# Sheet1.net
KiCad netlist of a schematic drawn in Altium Designer
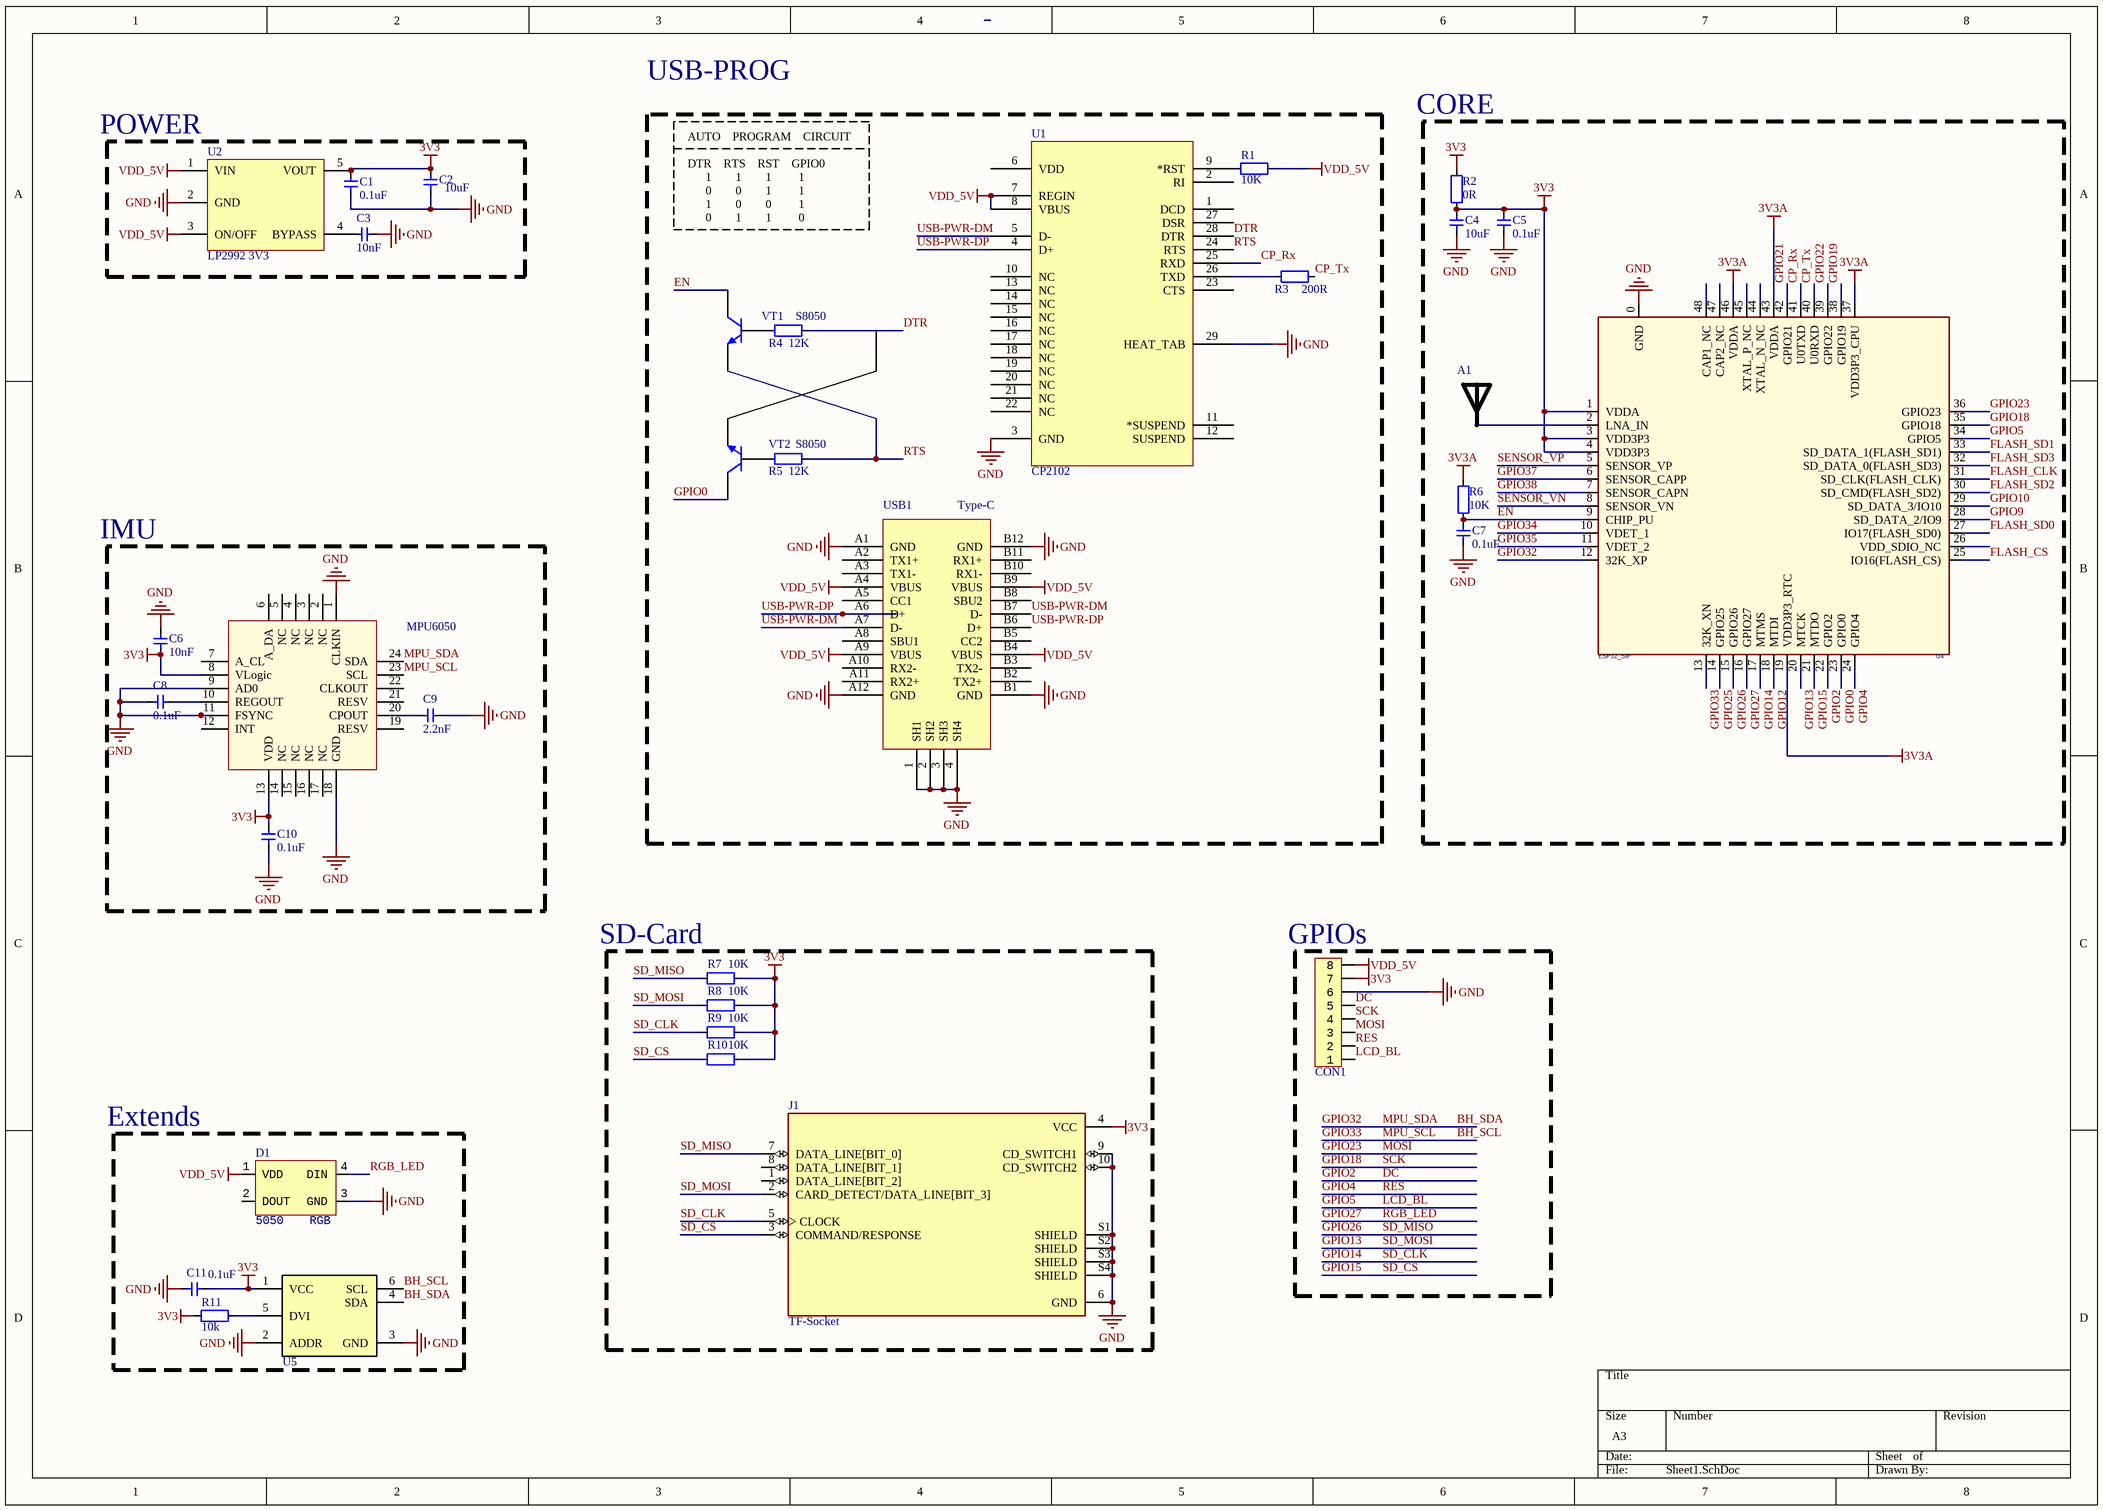
[diagram p0: Sheet1.SchDoc]

(export (version "E")
  (design (tool "Eeschema 10.0.6"))
  (components
    (comp (ref "A1")
      (value "RAINSUN")
      (footprint "ANT-Rainsun-AN5120")
      (libsource (lib "MainBoard") (part "ANT-Rainsun-AP5120"))
    )
    (comp (ref "C1")
      (value "0.1uF")
      (footprint "CAP_0402")
      (description "Capacitor")
      (libsource (lib "MainBoard") (part "电容-0402_3"))
    )
    (comp (ref "C2")
      (value "10uF")
      (footprint "CAP_0402")
      (description "Capacitor")
      (libsource (lib "MainBoard") (part "电容-0402_3"))
    )
    (comp (ref "C3")
      (value "10nF")
      (footprint "CAP_0402")
      (description "Capacitor")
      (libsource (lib "MainBoard") (part "电容-0402_3"))
    )
    (comp (ref "C4")
      (value "10uF")
      (footprint "CAP_0402")
      (description "Capacitor")
      (libsource (lib "MainBoard") (part "电容-0402_1"))
    )
    (comp (ref "C5")
      (value "0.1uF")
      (footprint "CAP_0402")
      (description "Capacitor")
      (libsource (lib "MainBoard") (part "电容-0402_1"))
    )
    (comp (ref "C6")
      (value "10nF")
      (footprint "CAP_0402")
      (description "Capacitor")
      (libsource (lib "MainBoard") (part "电容-0402"))
    )
    (comp (ref "C7")
      (value "0.1uF")
      (footprint "CAP_0402")
      (description "Capacitor")
      (libsource (lib "MainBoard") (part "电容-0402_1"))
    )
    (comp (ref "C8")
      (value "0.1uF")
      (footprint "CAP_0402")
      (description "Capacitor")
      (libsource (lib "MainBoard") (part "电容-0402"))
    )
    (comp (ref "C9")
      (value "2.2nF")
      (footprint "CAP_0402")
      (description "Capacitor")
      (libsource (lib "MainBoard") (part "电容-0402"))
    )
    (comp (ref "C10")
      (value "0.1uF")
      (footprint "CAP_0402")
      (description "Capacitor")
      (libsource (lib "MainBoard") (part "电容-0402"))
    )
    (comp (ref "C11")
      (value "0.1uF")
      (footprint "CAP_0402")
      (description "Capacitor")
      (libsource (lib "MainBoard") (part "电容-0402"))
    )
    (comp (ref "CON1")
      (value "FFC_0.5_8")
      (footprint "FFC_0.5_8")
      (description "FFC")
      (libsource (lib "MainBoard") (part "FFC_0.5_8"))
    )
    (comp (ref "D1")
      (value "RGB")
      (footprint "LED_5050_WS2812B")
      (description "LED")
      (fields (field (name "TYPE") "5050"))
      (libsource (lib "MainBoard") (part "LED_5050_WS2812B"))
    )
    (comp (ref "J1")
      (value "TF-Socket")
      (footprint "TF-Card-Amphenol with TF")
      (description "10 _8 + 2_ Position Card Connector Secure Digital - microSDâ„¢ Surface Mount, Right Angle Gold")
      (fields (field (name "MP") "1140084168") (field (name "MF") "Amphenol Commercial Products"))
      (libsource (lib "MainBoard") (part "TF-Socket"))
    )
    (comp (ref "R1")
      (value "10K")
      (footprint "RES_0402")
      (description "Resistor")
      (libsource (lib "MainBoard") (part "电阻-0402_1"))
    )
    (comp (ref "R2")
      (value "0R")
      (footprint "RES_0402")
      (description "Resistor")
      (libsource (lib "") (part "电阻-0402_1_1"))
    )
    (comp (ref "R3")
      (value "200R")
      (footprint "RES_0402")
      (description "Resistor")
      (libsource (lib "MainBoard") (part "电阻-0402_1"))
    )
    (comp (ref "R4")
      (value "12K")
      (footprint "RES_0402")
      (description "Resistor")
      (libsource (lib "MainBoard") (part "电阻-0402_1"))
    )
    (comp (ref "R5")
      (value "12K")
      (footprint "RES_0402")
      (description "Resistor")
      (libsource (lib "MainBoard") (part "电阻-0402_1"))
    )
    (comp (ref "R6")
      (value "10K")
      (footprint "RES_0402")
      (description "Resistor")
      (libsource (lib "") (part "电阻-0402_1_1"))
    )
    (comp (ref "R7")
      (value "10K")
      (footprint "RES_0402")
      (description "Resistor")
      (libsource (lib "MainBoard") (part "电阻-0402"))
    )
    (comp (ref "R8")
      (value "10K")
      (footprint "RES_0402")
      (description "Resistor")
      (libsource (lib "MainBoard") (part "电阻-0402"))
    )
    (comp (ref "R9")
      (value "10K")
      (footprint "RES_0402")
      (description "Resistor")
      (libsource (lib "MainBoard") (part "电阻-0402"))
    )
    (comp (ref "R10")
      (value "10K")
      (footprint "RES_0402")
      (description "Resistor")
      (libsource (lib "MainBoard") (part "电阻-0402"))
    )
    (comp (ref "R11")
      (value "10k")
      (footprint "RES_0402")
      (description "Resistor")
      (libsource (lib "MainBoard") (part "电阻-0402"))
    )
    (comp (ref "U1")
      (value "CP2102")
      (footprint "QFN-28")
      (description "USB转TTL")
      (libsource (lib "MainBoard") (part "CP2102"))
    )
    (comp (ref "U2")
      (value "LP2992 3V3")
      (footprint "SOT23-5")
      (description "LDO")
      (libsource (lib "MainBoard") (part "LP2992"))
    )
    (comp (ref "U3")
      (value "MPU6050")
      (footprint "QFN-24")
      (description "六轴传感器")
      (libsource (lib "MainBoard") (part "MPU6050"))
    )
    (comp (ref "U4")
      (value "ESP32_SIP")
      (footprint "QFN-48_7X7")
      (libsource (lib "MainBoard") (part "ESP32-PICO"))
    )
    (comp (ref "U5")
      (value "BH1750FVI-TR")
      (footprint "BH1750FVI")
      (libsource (lib "MainBoard") (part "BH1750FVI-TR"))
    )
    (comp (ref "USB1")
      (value "Type-C")
      (footprint "Type-C-TOP")
      (libsource (lib "MainBoard") (part "USB-Type-C-TOP"))
    )
    (comp (ref "VT1")
      (value "S8050")
      (footprint "SMT_TRIODE_NPN")
      (description "Surface mount NPN transistor, package SOT-23")
      (libsource (lib "MainBoard") (part "SMT_TRIODE_NPN"))
    )
    (comp (ref "VT2")
      (value "S8050")
      (footprint "SMT_TRIODE_NPN")
      (description "Surface mount NPN transistor, package SOT-23")
      (libsource (lib "MainBoard") (part "SMT_TRIODE_NPN"))
    )
  )
  (nets
    (net (code "1") (name "/BH_SCL") (class "Default")
      (node (ref "U3") (pin "23") (pinfunction "SCL_23") (pintype "passive"))
      (node (ref "U4") (pin "13") (pinfunction "32K_XN_13") (pintype "passive"))
      (node (ref "U5") (pin "6") (pinfunction "SCL_6") (pintype "passive"))
    )
    (net (code "2") (name "/BH_SDA") (class "Default")
      (node (ref "U3") (pin "24") (pinfunction "SDA_24") (pintype "passive"))
      (node (ref "U4") (pin "12") (pinfunction "32K_XP_12") (pintype "passive"))
      (node (ref "U5") (pin "4") (pinfunction "SDA_4") (pintype "passive"))
    )
    (net (code "3") (name "/CP_Rx") (class "Default")
      (node (ref "U1") (pin "25") (pinfunction "RXD_25") (pintype "passive"))
      (node (ref "U4") (pin "41") (pinfunction "U0TXD_41") (pintype "power_in"))
    )
    (net (code "4") (name "/CP_Tx") (class "Default")
      (node (ref "R3") (pin "1") (pinfunction "1_1") (pintype "passive"))
      (node (ref "U4") (pin "40") (pinfunction "U0RXD_40") (pintype "power_in"))
    )
    (net (code "5") (name "/DC") (class "Default")
      (node (ref "CON1") (pin "5") (pinfunction "5_5") (pintype "passive"))
      (node (ref "U4") (pin "22") (pinfunction "GPIO2_22") (pintype "passive"))
    )
    (net (code "6") (name "/DTR") (class "Default")
      (node (ref "R4") (pin "1") (pinfunction "1_1") (pintype "passive"))
      (node (ref "U1") (pin "28") (pinfunction "DTR_28") (pintype "passive"))
    )
    (net (code "7") (name "/EN") (class "Default")
      (node (ref "C7") (pin "1") (pinfunction "1_1") (pintype "passive"))
      (node (ref "R6") (pin "1") (pinfunction "1_1") (pintype "passive"))
      (node (ref "U4") (pin "9") (pinfunction "CHIP_PU_9") (pintype "passive"))
      (node (ref "VT1") (pin "3") (pinfunction "C_3") (pintype "passive"))
    )
    (net (code "8") (name "/FLASH_CLK") (class "Default")
      (node (ref "U4") (pin "31") (pinfunction "SD_CLK(FLASH_CLK)_31") (pintype "passive"))
    )
    (net (code "9") (name "/FLASH_CS") (class "Default")
      (node (ref "U4") (pin "25") (pinfunction "IO16(FLASH_CS)_25") (pintype "passive"))
    )
    (net (code "10") (name "/FLASH_SD0") (class "Default")
      (node (ref "U4") (pin "27") (pinfunction "IO17(FLASH_SD0)_27") (pintype "passive"))
    )
    (net (code "11") (name "/FLASH_SD1") (class "Default")
      (node (ref "U4") (pin "33") (pinfunction "SD_DATA_1(FLASH_SD1)_33") (pintype "passive"))
    )
    (net (code "12") (name "/FLASH_SD2") (class "Default")
      (node (ref "U4") (pin "30") (pinfunction "SD_CMD(FLASH_SD2)_30") (pintype "passive"))
    )
    (net (code "13") (name "/FLASH_SD3") (class "Default")
      (node (ref "U4") (pin "32") (pinfunction "SD_DATA_0(FLASH_SD3)_32") (pintype "passive"))
    )
    (net (code "14") (name "/GPIO0") (class "Default")
      (node (ref "U4") (pin "23") (pinfunction "GPIO0_23") (pintype "passive"))
      (node (ref "VT2") (pin "3") (pinfunction "C_3") (pintype "passive"))
    )
    (net (code "15") (name "/GPIO4") (class "Default")
      (node (ref "CON1") (pin "2") (pinfunction "2_2") (pintype "passive"))
      (node (ref "U4") (pin "24") (pinfunction "GPIO4_24") (pintype "passive"))
    )
    (net (code "16") (name "/GPIO5") (class "Default")
      (node (ref "CON1") (pin "1") (pinfunction "1_1") (pintype "passive"))
      (node (ref "U4") (pin "34") (pinfunction "GPIO5_34") (pintype "passive"))
    )
    (net (code "17") (name "/GPIO9") (class "Default")
      (node (ref "U4") (pin "28") (pinfunction "SD_DATA_2/IO9_28") (pintype "passive"))
    )
    (net (code "18") (name "/GPIO10") (class "Default")
      (node (ref "U4") (pin "29") (pinfunction "SD_DATA_3/IO10_29") (pintype "passive"))
    )
    (net (code "19") (name "/GPIO12") (class "Default")
      (node (ref "U4") (pin "18") (pinfunction "MTDI_18") (pintype "passive"))
    )
    (net (code "20") (name "/GPIO13") (class "Default")
      (node (ref "J1") (pin "2") (pinfunction "CARD_DETECT/DATA_LINE[BIT_3]_2") (pintype "bidirectional"))
      (node (ref "R8") (pin "1") (pinfunction "1_1") (pintype "passive"))
      (node (ref "U4") (pin "20") (pinfunction "MTCK_20") (pintype "passive"))
    )
    (net (code "21") (name "/GPIO14") (class "Default")
      (node (ref "J1") (pin "5") (pinfunction "CLOCK_5") (pintype "bidirectional"))
      (node (ref "R9") (pin "1") (pinfunction "1_1") (pintype "passive"))
      (node (ref "U4") (pin "17") (pinfunction "MTMS_17") (pintype "passive"))
    )
    (net (code "22") (name "/GPIO15") (class "Default")
      (node (ref "J1") (pin "3") (pinfunction "COMMAND/RESPONSE_3") (pintype "bidirectional"))
      (node (ref "R10") (pin "1") (pinfunction "1_1") (pintype "passive"))
      (node (ref "U4") (pin "21") (pinfunction "MTDO_21") (pintype "passive"))
    )
    (net (code "23") (name "/GPIO18") (class "Default")
      (node (ref "CON1") (pin "4") (pinfunction "4_4") (pintype "passive"))
      (node (ref "U4") (pin "35") (pinfunction "GPIO18_35") (pintype "passive"))
    )
    (net (code "24") (name "/GPIO19") (class "Default")
      (node (ref "U4") (pin "38") (pinfunction "GPIO19_38") (pintype "passive"))
    )
    (net (code "25") (name "/GPIO21") (class "Default")
      (node (ref "U4") (pin "42") (pinfunction "GPIO21_42") (pintype "passive"))
    )
    (net (code "26") (name "/GPIO22") (class "Default")
      (node (ref "U4") (pin "39") (pinfunction "GPIO22_39") (pintype "passive"))
    )
    (net (code "27") (name "/GPIO23") (class "Default")
      (node (ref "CON1") (pin "3") (pinfunction "3_3") (pintype "passive"))
      (node (ref "U4") (pin "36") (pinfunction "GPIO23_36") (pintype "passive"))
    )
    (net (code "28") (name "/GPIO25") (class "Default")
      (node (ref "U4") (pin "14") (pinfunction "GPIO25_14") (pintype "passive"))
    )
    (net (code "29") (name "/GPIO26") (class "Default")
      (node (ref "J1") (pin "7") (pinfunction "DATA_LINE[BIT_0]_7") (pintype "bidirectional"))
      (node (ref "R7") (pin "1") (pinfunction "1_1") (pintype "passive"))
      (node (ref "U4") (pin "15") (pinfunction "GPIO26_15") (pintype "passive"))
    )
    (net (code "30") (name "/GPIO27") (class "Default")
      (node (ref "D1") (pin "4") (pinfunction "DIN_4") (pintype "passive"))
      (node (ref "U4") (pin "16") (pinfunction "GPIO27_16") (pintype "passive"))
    )
    (net (code "31") (name "/GPIO34") (class "Default")
      (node (ref "U4") (pin "10") (pinfunction "VDET_1_10") (pintype "passive"))
    )
    (net (code "32") (name "/GPIO35") (class "Default")
      (node (ref "U4") (pin "11") (pinfunction "VDET_2_11") (pintype "passive"))
    )
    (net (code "33") (name "/GPIO37") (class "Default")
      (node (ref "U4") (pin "6") (pinfunction "SENSOR_CAPP_6") (pintype "passive"))
    )
    (net (code "34") (name "/GPIO38") (class "Default")
      (node (ref "U4") (pin "7") (pinfunction "SENSOR_CAPN_7") (pintype "passive"))
    )
    (net (code "35") (name "/RTS") (class "Default")
      (node (ref "R5") (pin "1") (pinfunction "1_1") (pintype "passive"))
      (node (ref "U1") (pin "24") (pinfunction "RTS_24") (pintype "passive"))
      (node (ref "VT1") (pin "2") (pinfunction "E_2") (pintype "passive"))
    )
    (net (code "36") (name "/SENSOR_VN") (class "Default")
      (node (ref "U4") (pin "8") (pinfunction "SENSOR_VN_8") (pintype "passive"))
    )
    (net (code "37") (name "/SENSOR_VP") (class "Default")
      (node (ref "U4") (pin "5") (pinfunction "SENSOR_VP_5") (pintype "passive"))
    )
    (net (code "38") (name "/USB-PWR-DM") (class "Default")
      (node (ref "U1") (pin "5") (pinfunction "D-_5") (pintype "passive"))
      (node (ref "USB1") (pin "A7") (pinfunction "D-_A7") (pintype "passive"))
      (node (ref "USB1") (pin "B7") (pinfunction "D-_B7") (pintype "passive"))
    )
    (net (code "39") (name "/USB-PWR-DP") (class "Default")
      (node (ref "U1") (pin "4") (pinfunction "D+_4") (pintype "passive"))
      (node (ref "USB1") (pin "A6") (pinfunction "D+_A6") (pintype "passive"))
      (node (ref "USB1") (pin "B6") (pinfunction "D+_B6") (pintype "passive"))
    )
    (net (code "40") (name "3V3") (class "Default")
      (node (ref "C1") (pin "2") (pinfunction "2_2") (pintype "passive"))
      (node (ref "C10") (pin "1") (pinfunction "1_1") (pintype "passive"))
      (node (ref "C11") (pin "1") (pinfunction "1_1") (pintype "passive"))
      (node (ref "C2") (pin "2") (pinfunction "2_2") (pintype "passive"))
      (node (ref "C4") (pin "1") (pinfunction "1_1") (pintype "passive"))
      (node (ref "C5") (pin "1") (pinfunction "1_1") (pintype "passive"))
      (node (ref "C6") (pin "1") (pinfunction "1_1") (pintype "passive"))
      (node (ref "CON1") (pin "7") (pinfunction "7_7") (pintype "passive"))
      (node (ref "J1") (pin "4") (pinfunction "VCC_4") (pintype "power_in"))
      (node (ref "R10") (pin "2") (pinfunction "2_2") (pintype "passive"))
      (node (ref "R11") (pin "1") (pinfunction "1_1") (pintype "passive"))
      (node (ref "R2") (pin "1") (pinfunction "1_1") (pintype "passive"))
      (node (ref "R2") (pin "2") (pinfunction "2_2") (pintype "passive"))
      (node (ref "R7") (pin "2") (pinfunction "2_2") (pintype "passive"))
      (node (ref "R8") (pin "2") (pinfunction "2_2") (pintype "passive"))
      (node (ref "R9") (pin "2") (pinfunction "2_2") (pintype "passive"))
      (node (ref "U2") (pin "5") (pinfunction "VOUT_5") (pintype "passive"))
      (node (ref "U3") (pin "13") (pinfunction "VDD_13") (pintype "passive"))
      (node (ref "U3") (pin "8") (pinfunction "VLogic_8") (pintype "passive"))
      (node (ref "U4") (pin "1") (pinfunction "VDDA_1") (pintype "power_in"))
      (node (ref "U4") (pin "3") (pinfunction "VDD3P3_3") (pintype "power_in"))
      (node (ref "U4") (pin "4") (pinfunction "VDD3P3_4") (pintype "power_in"))
      (node (ref "U5") (pin "1") (pinfunction "VCC_1") (pintype "passive"))
    )
    (net (code "41") (name "3V3A") (class "Default")
      (node (ref "R6") (pin "2") (pinfunction "2_2") (pintype "passive"))
      (node (ref "U4") (pin "19") (pinfunction "VDD3P3_RTC_19") (pintype "power_in"))
      (node (ref "U4") (pin "37") (pinfunction "VDD3P3_CPU_37") (pintype "power_in"))
      (node (ref "U4") (pin "43") (pinfunction "VDDA_43") (pintype "power_in"))
      (node (ref "U4") (pin "46") (pinfunction "VDDA_46") (pintype "power_in"))
    )
    (net (code "42") (name "GND") (class "Default")
      (node (ref "C1") (pin "1") (pinfunction "1_1") (pintype "passive"))
      (node (ref "C10") (pin "2") (pinfunction "2_2") (pintype "passive"))
      (node (ref "C11") (pin "2") (pinfunction "2_2") (pintype "passive"))
      (node (ref "C2") (pin "1") (pinfunction "1_1") (pintype "passive"))
      (node (ref "C3") (pin "2") (pinfunction "2_2") (pintype "passive"))
      (node (ref "C4") (pin "2") (pinfunction "2_2") (pintype "passive"))
      (node (ref "C5") (pin "2") (pinfunction "2_2") (pintype "passive"))
      (node (ref "C6") (pin "2") (pinfunction "2_2") (pintype "passive"))
      (node (ref "C7") (pin "2") (pinfunction "2_2") (pintype "passive"))
      (node (ref "C8") (pin "1") (pinfunction "1_1") (pintype "passive"))
      (node (ref "C9") (pin "2") (pinfunction "2_2") (pintype "passive"))
      (node (ref "CON1") (pin "6") (pinfunction "6_6") (pintype "passive"))
      (node (ref "D1") (pin "3") (pinfunction "GND_3") (pintype "passive"))
      (node (ref "J1") (pin "10") (pinfunction "CD_SWITCH2_10") (pintype "bidirectional"))
      (node (ref "J1") (pin "6") (pinfunction "GND_6") (pintype "power_in"))
      (node (ref "J1") (pin "9") (pinfunction "CD_SWITCH1_9") (pintype "bidirectional"))
      (node (ref "J1") (pin "S1") (pinfunction "SHIELD_S1") (pintype "passive"))
      (node (ref "J1") (pin "S2") (pinfunction "SHIELD_S2") (pintype "passive"))
      (node (ref "J1") (pin "S3") (pinfunction "SHIELD_S3") (pintype "passive"))
      (node (ref "J1") (pin "S4") (pinfunction "SHIELD_S4") (pintype "passive"))
      (node (ref "U1") (pin "29") (pinfunction "HEAT_TAB_29") (pintype "passive"))
      (node (ref "U1") (pin "3") (pinfunction "GND_3") (pintype "passive"))
      (node (ref "U2") (pin "2") (pinfunction "GND_2") (pintype "passive"))
      (node (ref "U3") (pin "1") (pinfunction "CLKIN_1") (pintype "passive"))
      (node (ref "U3") (pin "11") (pinfunction "FSYNC_11") (pintype "passive"))
      (node (ref "U3") (pin "18") (pinfunction "GND_18") (pintype "passive"))
      (node (ref "U3") (pin "9") (pinfunction "AD0_9") (pintype "passive"))
      (node (ref "U4") (pin "0") (pinfunction "GND_0") (pintype "power_in"))
      (node (ref "U5") (pin "2") (pinfunction "ADDR_2") (pintype "passive"))
      (node (ref "U5") (pin "3") (pinfunction "GND_3") (pintype "passive"))
      (node (ref "USB1") (pin "1") (pinfunction "SH1_1") (pintype "passive"))
      (node (ref "USB1") (pin "2") (pinfunction "SH2_2") (pintype "passive"))
      (node (ref "USB1") (pin "3") (pinfunction "SH3_3") (pintype "passive"))
      (node (ref "USB1") (pin "4") (pinfunction "SH4_4") (pintype "passive"))
      (node (ref "USB1") (pin "A1") (pinfunction "GND_A1") (pintype "passive"))
      (node (ref "USB1") (pin "A12") (pinfunction "GND_A12") (pintype "passive"))
      (node (ref "USB1") (pin "B1") (pinfunction "GND_B1") (pintype "passive"))
      (node (ref "USB1") (pin "B12") (pinfunction "GND_B12") (pintype "passive"))
    )
    (net (code "43") (name "Net-(U1-*RST)") (class "Default")
      (node (ref "R1") (pin "2") (pinfunction "2_2") (pintype "passive"))
      (node (ref "U1") (pin "9") (pinfunction "*RST_9") (pintype "passive"))
    )
    (net (code "44") (name "Net-(U1-TXD)") (class "Default")
      (node (ref "R3") (pin "2") (pinfunction "2_2") (pintype "passive"))
      (node (ref "U1") (pin "26") (pinfunction "TXD_26") (pintype "passive"))
    )
    (net (code "45") (name "Net-(U2-BYPASS)") (class "Default")
      (node (ref "C3") (pin "1") (pinfunction "1_1") (pintype "passive"))
      (node (ref "U2") (pin "4") (pinfunction "BYPASS_4") (pintype "passive"))
    )
    (net (code "46") (name "Net-(U3-CPOUT)") (class "Default")
      (node (ref "C9") (pin "1") (pinfunction "1_1") (pintype "passive"))
      (node (ref "U3") (pin "20") (pinfunction "CPOUT_20") (pintype "passive"))
    )
    (net (code "47") (name "Net-(U3-REGOUT)") (class "Default")
      (node (ref "C8") (pin "2") (pinfunction "2_2") (pintype "passive"))
      (node (ref "U3") (pin "10") (pinfunction "REGOUT_10") (pintype "passive"))
    )
    (net (code "48") (name "Net-(U4-LNA_IN)") (class "Default")
      (node (ref "A1") (pin "1") (pinfunction "1_1") (pintype "passive"))
      (node (ref "U4") (pin "2") (pinfunction "LNA_IN_2") (pintype "passive"))
    )
    (net (code "49") (name "Net-(U5-DVI)") (class "Default")
      (node (ref "R11") (pin "2") (pinfunction "2_2") (pintype "passive"))
      (node (ref "U5") (pin "5") (pinfunction "DVI_5") (pintype "passive"))
    )
    (net (code "50") (name "Net-(VT1-B)") (class "Default")
      (node (ref "R4") (pin "2") (pinfunction "2_2") (pintype "passive"))
      (node (ref "VT1") (pin "1") (pinfunction "B_1") (pintype "passive"))
    )
    (net (code "51") (name "Net-(VT2-B)") (class "Default")
      (node (ref "R5") (pin "2") (pinfunction "2_2") (pintype "passive"))
      (node (ref "VT2") (pin "1") (pinfunction "B_1") (pintype "passive"))
    )
    (net (code "52") (name "VDD_5V") (class "Default")
      (node (ref "CON1") (pin "8") (pinfunction "8_8") (pintype "passive"))
      (node (ref "D1") (pin "1") (pinfunction "VDD_1") (pintype "passive"))
      (node (ref "R1") (pin "1") (pinfunction "1_1") (pintype "passive"))
      (node (ref "U1") (pin "7") (pinfunction "REGIN_7") (pintype "passive"))
      (node (ref "U1") (pin "8") (pinfunction "VBUS_8") (pintype "passive"))
      (node (ref "U2") (pin "1") (pinfunction "VIN_1") (pintype "passive"))
      (node (ref "U2") (pin "3") (pinfunction "ON/OFF_3") (pintype "passive"))
      (node (ref "USB1") (pin "A4") (pinfunction "VBUS_A4") (pintype "passive"))
      (node (ref "USB1") (pin "A9") (pinfunction "VBUS_A9") (pintype "passive"))
      (node (ref "USB1") (pin "B4") (pinfunction "VBUS_B4") (pintype "passive"))
      (node (ref "USB1") (pin "B9") (pinfunction "VBUS_B9") (pintype "passive"))
    )
    (net (code "53") (name "unconnected-(D1-DOUT-Pad2)") (class "Default")
      (node (ref "D1") (pin "2") (pinfunction "DOUT_2") (pintype "passive"))
    )
    (net (code "54") (name "unconnected-(J1-DATA_LINE[BIT_1]-Pad8)") (class "Default")
      (node (ref "J1") (pin "8") (pinfunction "DATA_LINE[BIT_1]_8") (pintype "bidirectional"))
    )
    (net (code "55") (name "unconnected-(J1-DATA_LINE[BIT_2]-Pad1)") (class "Default")
      (node (ref "J1") (pin "1") (pinfunction "DATA_LINE[BIT_2]_1") (pintype "bidirectional"))
    )
    (net (code "56") (name "unconnected-(U1-*SUSPEND-Pad11)") (class "Default")
      (node (ref "U1") (pin "11") (pinfunction "*SUSPEND_11") (pintype "passive"))
    )
    (net (code "57") (name "unconnected-(U1-CTS-Pad23)") (class "Default")
      (node (ref "U1") (pin "23") (pinfunction "CTS_23") (pintype "passive"))
    )
    (net (code "58") (name "unconnected-(U1-DCD-Pad1)") (class "Default")
      (node (ref "U1") (pin "1") (pinfunction "DCD_1") (pintype "passive"))
    )
    (net (code "59") (name "unconnected-(U1-DSR-Pad27)") (class "Default")
      (node (ref "U1") (pin "27") (pinfunction "DSR_27") (pintype "passive"))
    )
    (net (code "60") (name "unconnected-(U1-NC-Pad10)") (class "Default")
      (node (ref "U1") (pin "10") (pinfunction "NC_10") (pintype "passive"))
    )
    (net (code "61") (name "unconnected-(U1-NC-Pad13)") (class "Default")
      (node (ref "U1") (pin "13") (pinfunction "NC_13") (pintype "passive"))
    )
    (net (code "62") (name "unconnected-(U1-NC-Pad14)") (class "Default")
      (node (ref "U1") (pin "14") (pinfunction "NC_14") (pintype "passive"))
    )
    (net (code "63") (name "unconnected-(U1-NC-Pad15)") (class "Default")
      (node (ref "U1") (pin "15") (pinfunction "NC_15") (pintype "passive"))
    )
    (net (code "64") (name "unconnected-(U1-NC-Pad16)") (class "Default")
      (node (ref "U1") (pin "16") (pinfunction "NC_16") (pintype "passive"))
    )
    (net (code "65") (name "unconnected-(U1-NC-Pad17)") (class "Default")
      (node (ref "U1") (pin "17") (pinfunction "NC_17") (pintype "passive"))
    )
    (net (code "66") (name "unconnected-(U1-NC-Pad18)") (class "Default")
      (node (ref "U1") (pin "18") (pinfunction "NC_18") (pintype "passive"))
    )
    (net (code "67") (name "unconnected-(U1-NC-Pad19)") (class "Default")
      (node (ref "U1") (pin "19") (pinfunction "NC_19") (pintype "passive"))
    )
    (net (code "68") (name "unconnected-(U1-NC-Pad20)") (class "Default")
      (node (ref "U1") (pin "20") (pinfunction "NC_20") (pintype "passive"))
    )
    (net (code "69") (name "unconnected-(U1-NC-Pad21)") (class "Default")
      (node (ref "U1") (pin "21") (pinfunction "NC_21") (pintype "passive"))
    )
    (net (code "70") (name "unconnected-(U1-NC-Pad22)") (class "Default")
      (node (ref "U1") (pin "22") (pinfunction "NC_22") (pintype "passive"))
    )
    (net (code "71") (name "unconnected-(U1-RI-Pad2)") (class "Default")
      (node (ref "U1") (pin "2") (pinfunction "RI_2") (pintype "passive"))
    )
    (net (code "72") (name "unconnected-(U1-SUSPEND-Pad12)") (class "Default")
      (node (ref "U1") (pin "12") (pinfunction "SUSPEND_12") (pintype "passive"))
    )
    (net (code "73") (name "unconnected-(U1-VDD-Pad6)") (class "Default")
      (node (ref "U1") (pin "6") (pinfunction "VDD_6") (pintype "passive"))
    )
    (net (code "74") (name "unconnected-(U3-A_CL-Pad7)") (class "Default")
      (node (ref "U3") (pin "7") (pinfunction "A_CL_7") (pintype "passive"))
    )
    (net (code "75") (name "unconnected-(U3-A_DA-Pad6)") (class "Default")
      (node (ref "U3") (pin "6") (pinfunction "A_DA_6") (pintype "passive"))
    )
    (net (code "76") (name "unconnected-(U3-CLKOUT-Pad22)") (class "Default")
      (node (ref "U3") (pin "22") (pinfunction "CLKOUT_22") (pintype "passive"))
    )
    (net (code "77") (name "unconnected-(U3-INT-Pad12)") (class "Default")
      (node (ref "U3") (pin "12") (pinfunction "INT_12") (pintype "passive"))
    )
    (net (code "78") (name "unconnected-(U3-NC-Pad2)") (class "Default")
      (node (ref "U3") (pin "2") (pinfunction "NC_2") (pintype "passive"))
    )
    (net (code "79") (name "unconnected-(U3-NC-Pad3)") (class "Default")
      (node (ref "U3") (pin "3") (pinfunction "NC_3") (pintype "passive"))
    )
    (net (code "80") (name "unconnected-(U3-NC-Pad4)") (class "Default")
      (node (ref "U3") (pin "4") (pinfunction "NC_4") (pintype "passive"))
    )
    (net (code "81") (name "unconnected-(U3-NC-Pad5)") (class "Default")
      (node (ref "U3") (pin "5") (pinfunction "NC_5") (pintype "passive"))
    )
    (net (code "82") (name "unconnected-(U3-NC-Pad14)") (class "Default")
      (node (ref "U3") (pin "14") (pinfunction "NC_14") (pintype "passive"))
    )
    (net (code "83") (name "unconnected-(U3-NC-Pad15)") (class "Default")
      (node (ref "U3") (pin "15") (pinfunction "NC_15") (pintype "passive"))
    )
    (net (code "84") (name "unconnected-(U3-NC-Pad16)") (class "Default")
      (node (ref "U3") (pin "16") (pinfunction "NC_16") (pintype "passive"))
    )
    (net (code "85") (name "unconnected-(U3-NC-Pad17)") (class "Default")
      (node (ref "U3") (pin "17") (pinfunction "NC_17") (pintype "passive"))
    )
    (net (code "86") (name "unconnected-(U3-RESV-Pad19)") (class "Default")
      (node (ref "U3") (pin "19") (pinfunction "RESV_19") (pintype "passive"))
    )
    (net (code "87") (name "unconnected-(U3-RESV-Pad21)") (class "Default")
      (node (ref "U3") (pin "21") (pinfunction "RESV_21") (pintype "passive"))
    )
    (net (code "88") (name "unconnected-(U4-CAP1_NC-Pad48)") (class "Default")
      (node (ref "U4") (pin "48") (pinfunction "CAP1_NC_48") (pintype "passive"))
    )
    (net (code "89") (name "unconnected-(U4-CAP2_NC-Pad47)") (class "Default")
      (node (ref "U4") (pin "47") (pinfunction "CAP2_NC_47") (pintype "passive"))
    )
    (net (code "90") (name "unconnected-(U4-VDD_SDIO_NC-Pad26)") (class "Default")
      (node (ref "U4") (pin "26") (pinfunction "VDD_SDIO_NC_26") (pintype "passive"))
    )
    (net (code "91") (name "unconnected-(U4-XTAL_N_NC-Pad44)") (class "Default")
      (node (ref "U4") (pin "44") (pinfunction "XTAL_N_NC_44") (pintype "passive"))
    )
    (net (code "92") (name "unconnected-(U4-XTAL_P_NC-Pad45)") (class "Default")
      (node (ref "U4") (pin "45") (pinfunction "XTAL_P_NC_45") (pintype "passive"))
    )
    (net (code "93") (name "unconnected-(USB1-CC1-PadA5)") (class "Default")
      (node (ref "USB1") (pin "A5") (pinfunction "CC1_A5") (pintype "passive"))
    )
    (net (code "94") (name "unconnected-(USB1-CC2-PadB5)") (class "Default")
      (node (ref "USB1") (pin "B5") (pinfunction "CC2_B5") (pintype "passive"))
    )
    (net (code "95") (name "unconnected-(USB1-RX1+-PadB11)") (class "Default")
      (node (ref "USB1") (pin "B11") (pinfunction "RX1+_B11") (pintype "passive"))
    )
    (net (code "96") (name "unconnected-(USB1-RX1--PadB10)") (class "Default")
      (node (ref "USB1") (pin "B10") (pinfunction "RX1-_B10") (pintype "passive"))
    )
    (net (code "97") (name "unconnected-(USB1-RX2+-PadA11)") (class "Default")
      (node (ref "USB1") (pin "A11") (pinfunction "RX2+_A11") (pintype "passive"))
    )
    (net (code "98") (name "unconnected-(USB1-RX2--PadA10)") (class "Default")
      (node (ref "USB1") (pin "A10") (pinfunction "RX2-_A10") (pintype "passive"))
    )
    (net (code "99") (name "unconnected-(USB1-SBU1-PadA8)") (class "Default")
      (node (ref "USB1") (pin "A8") (pinfunction "SBU1_A8") (pintype "passive"))
    )
    (net (code "100") (name "unconnected-(USB1-SBU2-PadB8)") (class "Default")
      (node (ref "USB1") (pin "B8") (pinfunction "SBU2_B8") (pintype "passive"))
    )
    (net (code "101") (name "unconnected-(USB1-TX1+-PadA2)") (class "Default")
      (node (ref "USB1") (pin "A2") (pinfunction "TX1+_A2") (pintype "passive"))
    )
    (net (code "102") (name "unconnected-(USB1-TX1--PadA3)") (class "Default")
      (node (ref "USB1") (pin "A3") (pinfunction "TX1-_A3") (pintype "passive"))
    )
    (net (code "103") (name "unconnected-(USB1-TX2+-PadB2)") (class "Default")
      (node (ref "USB1") (pin "B2") (pinfunction "TX2+_B2") (pintype "passive"))
    )
    (net (code "104") (name "unconnected-(USB1-TX2--PadB3)") (class "Default")
      (node (ref "USB1") (pin "B3") (pinfunction "TX2-_B3") (pintype "passive"))
    )
    (net (code "105") (name "unconnected-(VT2-E-Pad2)") (class "Default")
      (node (ref "VT2") (pin "2") (pinfunction "E_2") (pintype "passive"))
    )
  )
)
